# Apollon_ML_testing.net
KiCad netlist of a schematic drawn in EasyEDA
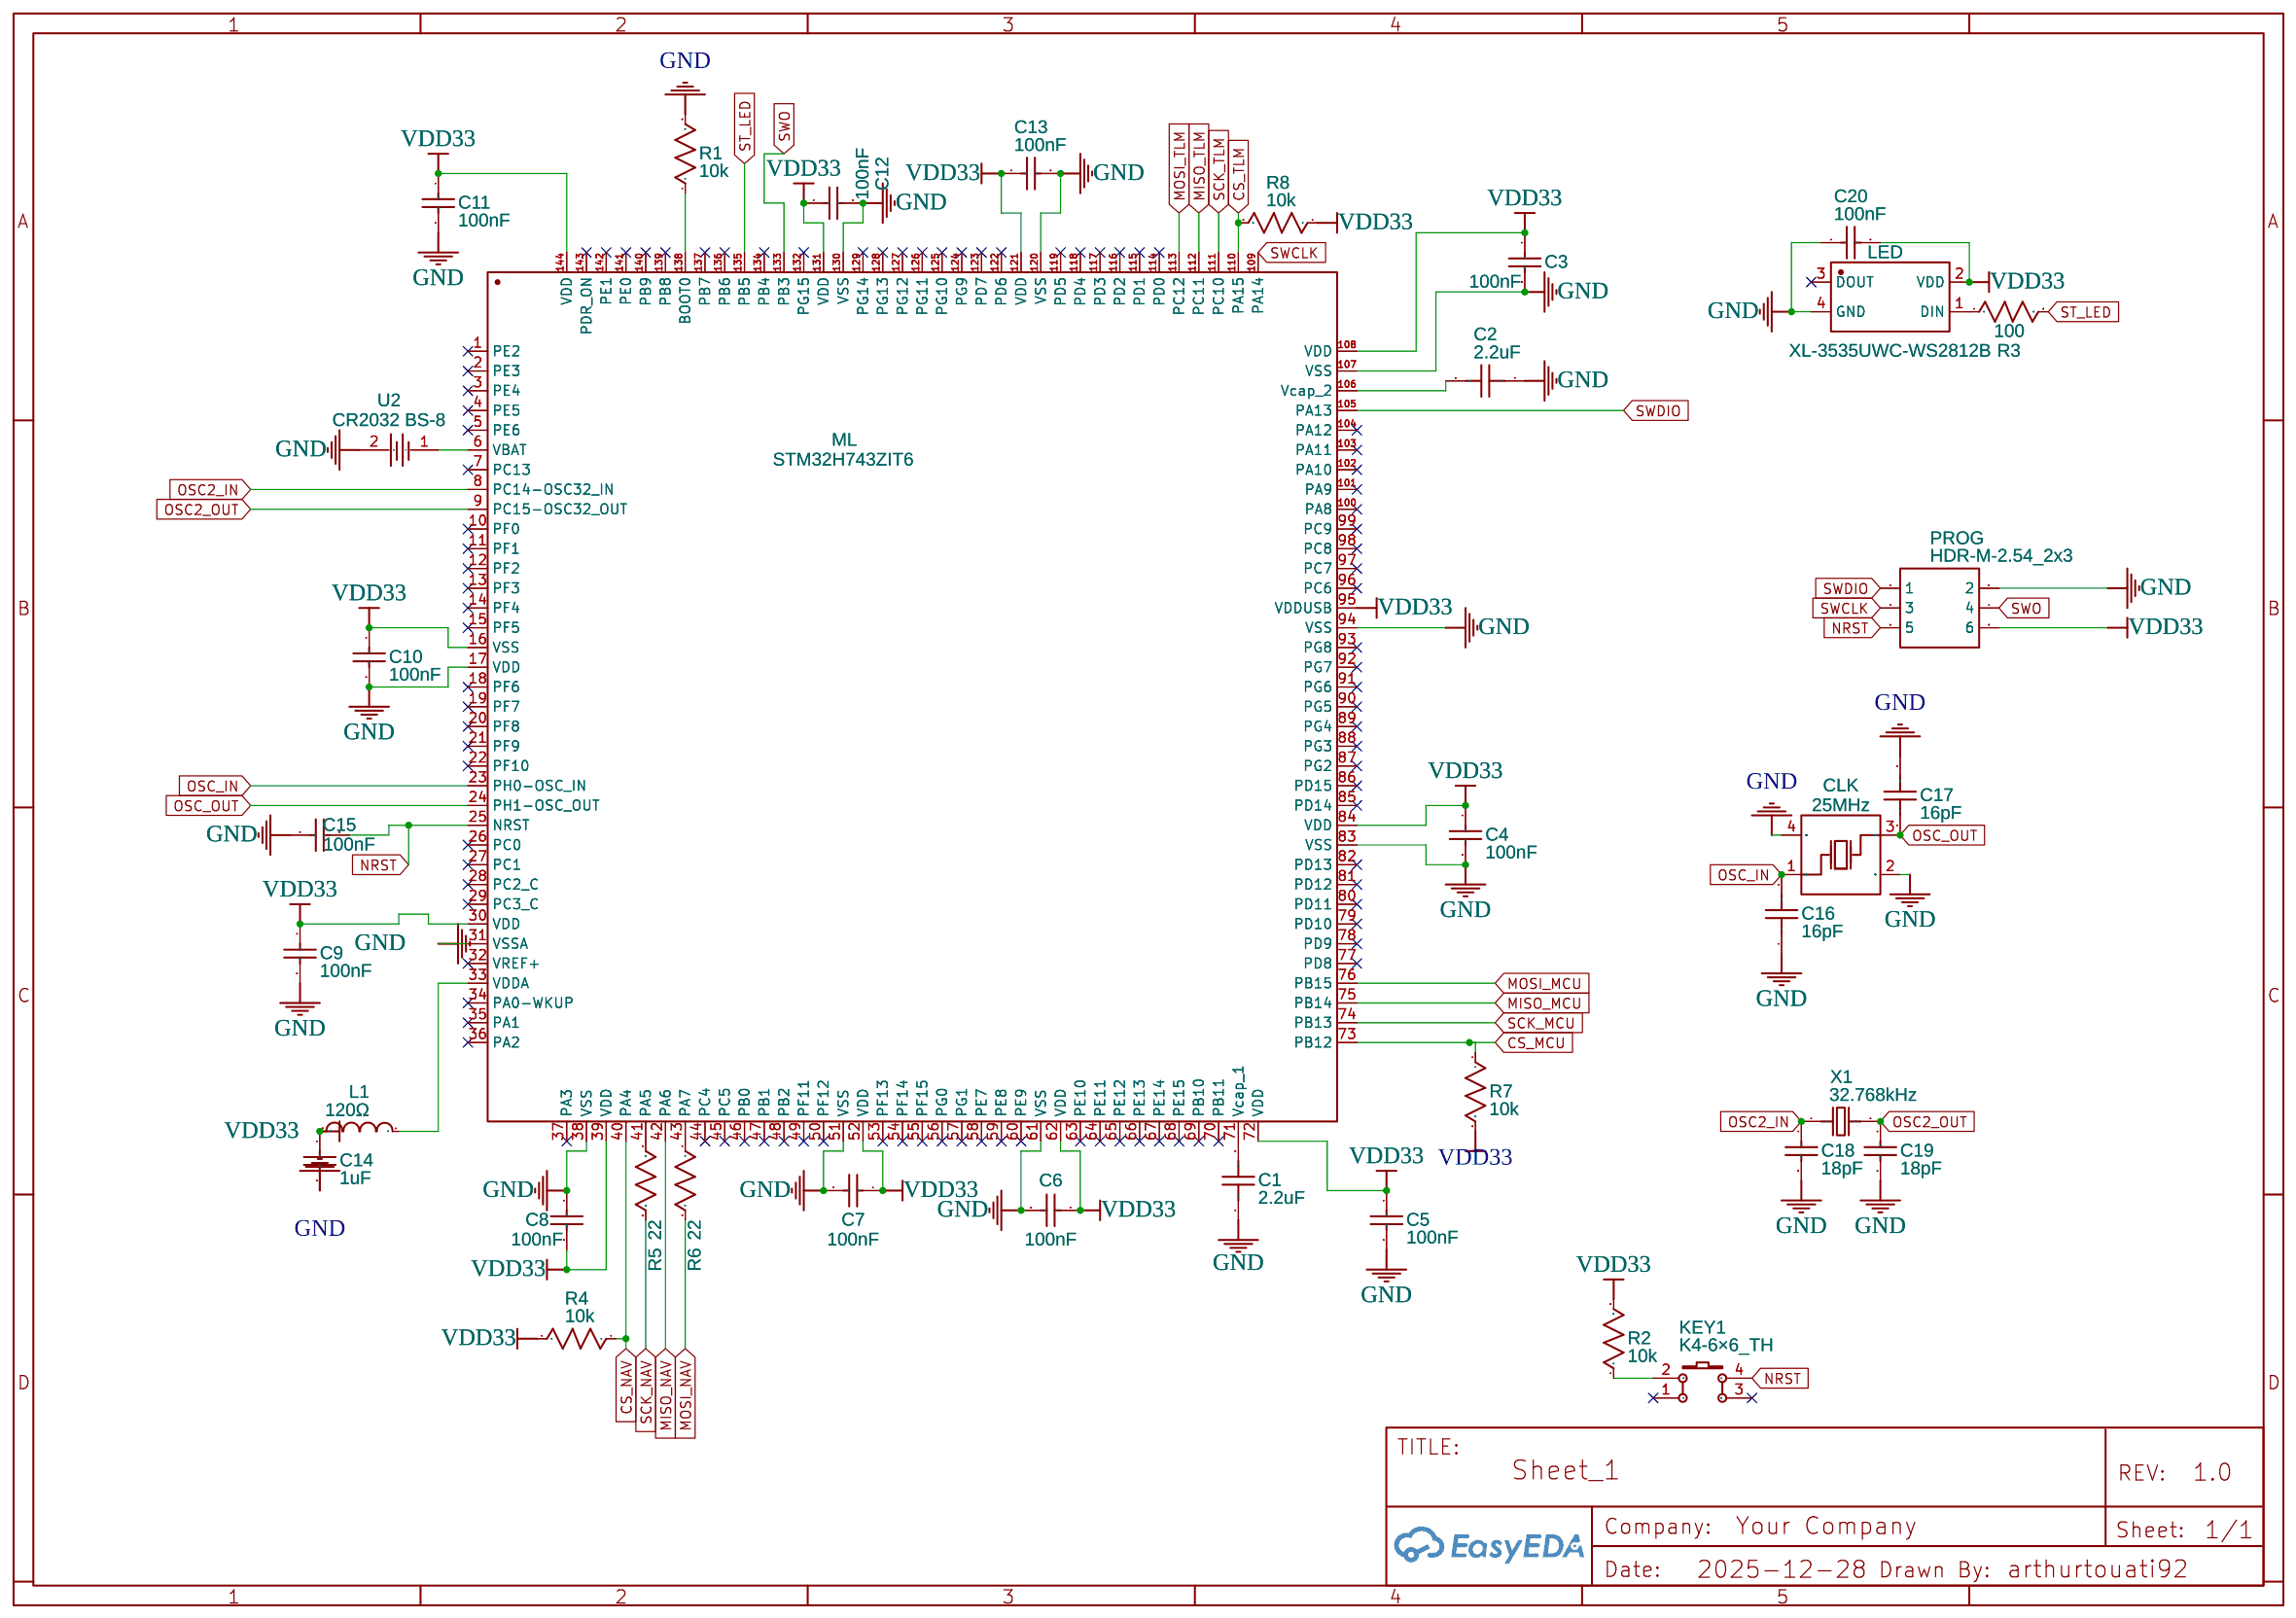
[diagram p0: schematic sheet]

(export (version "E")
  (design (tool "Eeschema 10.0.6"))
  (components
    (comp (ref "C1")
      (value "2.2uF")
      (fields
        (field (name "Manufacturer Part") "CL03A225MP3CRNC")
        (field (name "Manufacturer") "SAMSUNG(三星)")
      )
      (libsource (lib "") (part "CL03A225MP3CRNC_1"))
    )
    (comp (ref "C2")
      (value "2.2uF")
      (fields
        (field (name "Manufacturer Part") "CL03A225MP3CRNC")
        (field (name "Manufacturer") "SAMSUNG(三星)")
      )
      (libsource (lib "") (part "CL03A225MP3CRNC"))
    )
    (comp (ref "C3")
      (value "100nF")
      (fields
        (field (name "Manufacturer Part") "GRM033R61A104KE15D")
        (field (name "Manufacturer") "muRata(村田)")
      )
      (libsource (lib "") (part "GRM033R61A104KE15D"))
    )
    (comp (ref "C4")
      (value "100nF")
      (fields
        (field (name "Manufacturer Part") "GRM033R61A104KE15D")
        (field (name "Manufacturer") "muRata(村田)")
      )
      (libsource (lib "") (part "GRM033R61A104KE15D"))
    )
    (comp (ref "C5")
      (value "100nF")
      (fields
        (field (name "Manufacturer Part") "GRM033R61A104KE15D")
        (field (name "Manufacturer") "muRata(村田)")
      )
      (libsource (lib "") (part "GRM033R61A104KE15D"))
    )
    (comp (ref "C6")
      (value "100nF")
      (fields
        (field (name "Manufacturer Part") "GRM033R61A104KE15D")
        (field (name "Manufacturer") "muRata(村田)")
      )
      (libsource (lib "") (part "GRM033R61A104KE15D_2"))
    )
    (comp (ref "C7")
      (value "100nF")
      (fields
        (field (name "Manufacturer Part") "GRM033R61A104KE15D")
        (field (name "Manufacturer") "muRata(村田)")
      )
      (libsource (lib "") (part "GRM033R61A104KE15D_2"))
    )
    (comp (ref "C8")
      (value "100nF")
      (fields
        (field (name "Manufacturer Part") "GRM033R61A104KE15D")
        (field (name "Manufacturer") "muRata(村田)")
      )
      (libsource (lib "") (part "GRM033R61A104KE15D"))
    )
    (comp (ref "C9")
      (value "100nF")
      (fields
        (field (name "Manufacturer Part") "GRM033R61A104KE15D")
        (field (name "Manufacturer") "muRata(村田)")
      )
      (libsource (lib "") (part "GRM033R61A104KE15D"))
    )
    (comp (ref "C10")
      (value "100nF")
      (fields
        (field (name "Manufacturer Part") "GRM033R61A104KE15D")
        (field (name "Manufacturer") "muRata(村田)")
      )
      (libsource (lib "") (part "GRM033R61A104KE15D"))
    )
    (comp (ref "C11")
      (value "100nF")
      (fields
        (field (name "Manufacturer Part") "GRM033R61A104KE15D")
        (field (name "Manufacturer") "muRata(村田)")
      )
      (libsource (lib "") (part "GRM033R61A104KE15D"))
    )
    (comp (ref "C12")
      (value "100nF")
      (fields
        (field (name "Manufacturer Part") "GRM033R61A104KE15D")
        (field (name "Manufacturer") "muRata(村田)")
      )
      (libsource (lib "") (part "GRM033R61A104KE15D_1"))
    )
    (comp (ref "C13")
      (value "100nF")
      (fields
        (field (name "Manufacturer Part") "GRM033R61A104KE15D")
        (field (name "Manufacturer") "muRata(村田)")
      )
      (libsource (lib "") (part "GRM033R61A104KE15D_1"))
    )
    (comp (ref "C14")
      (value "1uF")
      (fields
        (field (name "Manufacturer Part") "CL03A105MQ3CSNH")
        (field (name "Manufacturer") "SAMSUNG(三星)")
      )
      (libsource (lib "") (part "CL03A105MQ3CSNH"))
    )
    (comp (ref "C15")
      (value "100nF")
      (fields
        (field (name "Manufacturer Part") "GRM033R61A104KE15D")
        (field (name "Manufacturer") "muRata(村田)")
      )
      (libsource (lib "") (part "GRM033R61A104KE15D_2"))
    )
    (comp (ref "C16")
      (value "16pF")
      (fields
        (field (name "Manufacturer Part") "GRM1555C1H160JA01D")
        (field (name "Manufacturer") "muRata(村田)")
      )
      (libsource (lib "") (part "GRM1555C1H160JA01D"))
    )
    (comp (ref "C17")
      (value "16pF")
      (fields
        (field (name "Manufacturer Part") "GRM1555C1H160JA01D")
        (field (name "Manufacturer") "muRata(村田)")
      )
      (libsource (lib "") (part "GRM1555C1H160JA01D"))
    )
    (comp (ref "C18")
      (value "18pF")
      (fields
        (field (name "Manufacturer Part") "GRM033R61A104KE15D")
        (field (name "Manufacturer") "muRata(村田)")
      )
      (libsource (lib "") (part "GRM033R61A104KE15D"))
    )
    (comp (ref "C19")
      (value "18pF")
      (fields
        (field (name "Manufacturer Part") "GRM033R61A104KE15D")
        (field (name "Manufacturer") "muRata(村田)")
      )
      (libsource (lib "") (part "GRM033R61A104KE15D"))
    )
    (comp (ref "C20")
      (value "100nF")
      (fields
        (field (name "Manufacturer Part") "GRM033R61A104KE15D")
        (field (name "Manufacturer") "muRata(村田)")
      )
      (libsource (lib "") (part "GRM033R61A104KE15D_1"))
    )
    (comp (ref "CLK")
      (value "25MHz")
      (fields
        (field (name "Manufacturer Part") "ABM8AIG-25.000MHZ-12-2Z-T3")
        (field (name "Manufacturer") "ABRACON")
      )
      (libsource (lib "") (part "ABM8AIG-25.000MHZ-12-2Z-T3"))
    )
    (comp (ref "KEY1")
      (value "K4-6×6_TH")
      (fields (field (name "Manufacturer Part") "K2-1102DP-E4SW-04") (field (name "Manufacturer") "韩国韩荣"))
      (libsource (lib "") (part "K4-6×6_TH"))
    )
    (comp (ref "L1")
      (value "120Ω")
      (fields (field (name "Manufacturer Part") "BLM03AG121SN1D") (field (name "Manufacturer") "muRata(村田)"))
      (libsource (lib "") (part "BLM03AG121SN1D"))
    )
    (comp (ref "LED")
      (value "XL-3535UWC-WS2812B")
      (fields
        (field (name "Manufacturer Part") "XL-3535UWC-2812B")
        (field (name "Manufacturer") "XINGLIGHT(成兴光)")
      )
      (libsource (lib "") (part "XL-3535UWC-WS2812B"))
    )
    (comp (ref "ML")
      (value "STM32H743ZIT6")
      (fields (field (name "Manufacturer") "ST(意法半导体)"))
      (libsource (lib "") (part "STM32H743ZIT6"))
    )
    (comp (ref "PROG") (value "HDR-M-2.54_2x3") (libsource (lib "") (part "HDR-M-2.54_2x3")))
    (comp (ref "R1") (value "10k") (libsource (lib "") (part "R_0201_US_2")))
    (comp (ref "R2") (value "10k") (libsource (lib "") (part "R_0201_US_2")))
    (comp (ref "R3") (value "100") (libsource (lib "") (part "R_0201_US_3")))
    (comp (ref "R4") (value "10k") (libsource (lib "") (part "R_0201_US_1")))
    (comp (ref "R5") (value "22") (libsource (lib "") (part "R_0201_US")))
    (comp (ref "R6") (value "22") (libsource (lib "") (part "R_0201_US")))
    (comp (ref "R7") (value "10k") (libsource (lib "") (part "R_0201_US")))
    (comp (ref "R8") (value "10k") (libsource (lib "") (part "R_0201_US_1")))
    (comp (ref "U2") (value "CR2032 BS-8") (libsource (lib "") (part "CR2032 BS-8")))
    (comp (ref "X1")
      (value "32.768kHz")
      (fields
        (field (name "Manufacturer Part") "SC-32S32.768kHz20PPM12.5pF")
        (field (name "Manufacturer") "Seiko(精工)")
      )
      (libsource (lib "") (part "SC-32S32.768kHz20PPM12.5pF"))
    )
  )
  (nets
    (net (code "1") (name "CS_MCU") (class "Default")
      (node (ref "ML") (pin "73") (pinfunction "PB12_73") (pintype "unspecified"))
      (node (ref "R7") (pin "1") (pinfunction "1_1") (pintype "unspecified"))
    )
    (net (code "2") (name "CS_NAV") (class "Default")
      (node (ref "ML") (pin "40") (pinfunction "PA4_40") (pintype "unspecified"))
      (node (ref "R4") (pin "1") (pinfunction "1_1") (pintype "unspecified"))
    )
    (net (code "3") (name "CS_TLM") (class "Default")
      (node (ref "ML") (pin "110") (pinfunction "PA15_110") (pintype "unspecified"))
      (node (ref "R8") (pin "2") (pinfunction "2_2") (pintype "unspecified"))
    )
    (net (code "4") (name "GND") (class "Default")
      (node (ref "C1") (pin "1") (pinfunction "1_1") (pintype "unspecified"))
      (node (ref "C10") (pin "2") (pinfunction "2_2") (pintype "input"))
      (node (ref "C11") (pin "2") (pinfunction "2_2") (pintype "input"))
      (node (ref "C12") (pin "2") (pinfunction "2_2") (pintype "input"))
      (node (ref "C13") (pin "2") (pinfunction "2_2") (pintype "input"))
      (node (ref "C14") (pin "2") (pinfunction "2_2") (pintype "input"))
      (node (ref "C15") (pin "2") (pinfunction "2_2") (pintype "input"))
      (node (ref "C16") (pin "1") (pinfunction "1_1") (pintype "unspecified"))
      (node (ref "C17") (pin "2") (pinfunction "2_2") (pintype "unspecified"))
      (node (ref "C18") (pin "2") (pinfunction "2_2") (pintype "input"))
      (node (ref "C19") (pin "2") (pinfunction "2_2") (pintype "input"))
      (node (ref "C2") (pin "1") (pinfunction "1_1") (pintype "unspecified"))
      (node (ref "C20") (pin "1") (pinfunction "1_1") (pintype "input"))
      (node (ref "C3") (pin "2") (pinfunction "2_2") (pintype "input"))
      (node (ref "C4") (pin "2") (pinfunction "2_2") (pintype "input"))
      (node (ref "C5") (pin "2") (pinfunction "2_2") (pintype "input"))
      (node (ref "C6") (pin "2") (pinfunction "2_2") (pintype "input"))
      (node (ref "C7") (pin "2") (pinfunction "2_2") (pintype "input"))
      (node (ref "C8") (pin "1") (pinfunction "1_1") (pintype "input"))
      (node (ref "C9") (pin "2") (pinfunction "2_2") (pintype "input"))
      (node (ref "CLK") (pin "2") (pinfunction "GND_2") (pintype "unspecified"))
      (node (ref "CLK") (pin "4") (pinfunction "GND_4") (pintype "unspecified"))
      (node (ref "LED") (pin "4") (pinfunction "GND_4") (pintype "unspecified"))
      (node (ref "ML") (pin "107") (pinfunction "VSS_107") (pintype "unspecified"))
      (node (ref "ML") (pin "120") (pinfunction "VSS_120") (pintype "unspecified"))
      (node (ref "ML") (pin "130") (pinfunction "VSS_130") (pintype "unspecified"))
      (node (ref "ML") (pin "17") (pinfunction "VDD_17") (pintype "unspecified"))
      (node (ref "ML") (pin "31") (pinfunction "VSSA_31") (pintype "unspecified"))
      (node (ref "ML") (pin "38") (pinfunction "VSS_38") (pintype "unspecified"))
      (node (ref "ML") (pin "51") (pinfunction "VSS_51") (pintype "unspecified"))
      (node (ref "ML") (pin "61") (pinfunction "VSS_61") (pintype "unspecified"))
      (node (ref "ML") (pin "83") (pinfunction "VSS_83") (pintype "unspecified"))
      (node (ref "ML") (pin "94") (pinfunction "VSS_94") (pintype "unspecified"))
      (node (ref "PROG") (pin "2") (pinfunction "2_2") (pintype "input"))
      (node (ref "R1") (pin "2") (pinfunction "2_2") (pintype "unspecified"))
      (node (ref "U2") (pin "2") (pinfunction "+_2") (pintype "input"))
    )
    (net (code "5") (name "MISO_MCU") (class "Default")
      (node (ref "ML") (pin "75") (pinfunction "PB14_75") (pintype "unspecified"))
    )
    (net (code "6") (name "MISO_NAV") (class "Default")
      (node (ref "ML") (pin "42") (pinfunction "PA6_42") (pintype "unspecified"))
    )
    (net (code "7") (name "MISO_TLM") (class "Default")
      (node (ref "ML") (pin "112") (pinfunction "PC11_112") (pintype "unspecified"))
    )
    (net (code "8") (name "MOSI_MCU") (class "Default")
      (node (ref "ML") (pin "76") (pinfunction "PB15_76") (pintype "unspecified"))
    )
    (net (code "9") (name "MOSI_NAV") (class "Default")
      (node (ref "R6") (pin "2") (pinfunction "2_2") (pintype "unspecified"))
    )
    (net (code "10") (name "MOSI_TLM") (class "Default")
      (node (ref "ML") (pin "113") (pinfunction "PC12_113") (pintype "unspecified"))
    )
    (net (code "11") (name "NRST") (class "Default")
      (node (ref "C15") (pin "1") (pinfunction "1_1") (pintype "input"))
      (node (ref "KEY1") (pin "4") (pinfunction "4_4") (pintype "unspecified"))
      (node (ref "ML") (pin "25") (pinfunction "NRST_25") (pintype "unspecified"))
      (node (ref "PROG") (pin "5") (pinfunction "5_5") (pintype "input"))
    )
    (net (code "12") (name "Net-(KEY1-Pad2)") (class "Default")
      (node (ref "KEY1") (pin "2") (pinfunction "2_2") (pintype "unspecified"))
      (node (ref "R2") (pin "1") (pinfunction "1_1") (pintype "unspecified"))
    )
    (net (code "13") (name "Net-(LED-DIN)") (class "Default")
      (node (ref "LED") (pin "1") (pinfunction "DIN_1") (pintype "unspecified"))
      (node (ref "R3") (pin "1") (pinfunction "1_1") (pintype "unspecified"))
    )
    (net (code "14") (name "Net-(ML-BOOT0)") (class "Default")
      (node (ref "ML") (pin "138") (pinfunction "BOOT0_138") (pintype "unspecified"))
      (node (ref "R1") (pin "1") (pinfunction "1_1") (pintype "unspecified"))
    )
    (net (code "15") (name "Net-(ML-PA5)") (class "Default")
      (node (ref "ML") (pin "41") (pinfunction "PA5_41") (pintype "unspecified"))
      (node (ref "R5") (pin "1") (pinfunction "1_1") (pintype "unspecified"))
    )
    (net (code "16") (name "Net-(ML-PA7)") (class "Default")
      (node (ref "ML") (pin "43") (pinfunction "PA7_43") (pintype "unspecified"))
      (node (ref "R6") (pin "1") (pinfunction "1_1") (pintype "unspecified"))
    )
    (net (code "17") (name "Net-(ML-VBAT)") (class "Default")
      (node (ref "ML") (pin "6") (pinfunction "VBAT_6") (pintype "unspecified"))
      (node (ref "U2") (pin "1") (pinfunction "-_1") (pintype "input"))
    )
    (net (code "18") (name "Net-(ML-VDDA)") (class "Default")
      (node (ref "L1") (pin "1") (pinfunction "1_1") (pintype "unspecified"))
      (node (ref "ML") (pin "33") (pinfunction "VDDA_33") (pintype "unspecified"))
    )
    (net (code "19") (name "Net-(ML-Vcap_1)") (class "Default")
      (node (ref "C1") (pin "2") (pinfunction "2_2") (pintype "unspecified"))
      (node (ref "ML") (pin "71") (pinfunction "Vcap_1_71") (pintype "unspecified"))
    )
    (net (code "20") (name "Net-(ML-Vcap_2)") (class "Default")
      (node (ref "C2") (pin "2") (pinfunction "2_2") (pintype "unspecified"))
      (node (ref "ML") (pin "106") (pinfunction "Vcap_2_106") (pintype "unspecified"))
    )
    (net (code "21") (name "OSC2_IN") (class "Default")
      (node (ref "C18") (pin "1") (pinfunction "1_1") (pintype "input"))
      (node (ref "ML") (pin "8") (pinfunction "PC14-OSC32_IN_8") (pintype "unspecified"))
      (node (ref "X1") (pin "1") (pinfunction "1_1") (pintype "unspecified"))
    )
    (net (code "22") (name "OSC2_OUT") (class "Default")
      (node (ref "C19") (pin "1") (pinfunction "1_1") (pintype "input"))
      (node (ref "ML") (pin "9") (pinfunction "PC15-OSC32_OUT_9") (pintype "unspecified"))
      (node (ref "X1") (pin "2") (pinfunction "2_2") (pintype "unspecified"))
    )
    (net (code "23") (name "OSC_IN") (class "Default")
      (node (ref "C16") (pin "2") (pinfunction "2_2") (pintype "unspecified"))
      (node (ref "CLK") (pin "1") (pinfunction "OSC1_1") (pintype "unspecified"))
      (node (ref "ML") (pin "23") (pinfunction "PH0-OSC_IN_23") (pintype "unspecified"))
    )
    (net (code "24") (name "OSC_OUT") (class "Default")
      (node (ref "C17") (pin "1") (pinfunction "1_1") (pintype "unspecified"))
      (node (ref "CLK") (pin "3") (pinfunction "OSC2_3") (pintype "unspecified"))
      (node (ref "ML") (pin "24") (pinfunction "PH1-OSC_OUT_24") (pintype "unspecified"))
    )
    (net (code "25") (name "SCK_MCU") (class "Default")
      (node (ref "ML") (pin "74") (pinfunction "PB13_74") (pintype "unspecified"))
    )
    (net (code "26") (name "SCK_NAV") (class "Default")
      (node (ref "R5") (pin "2") (pinfunction "2_2") (pintype "unspecified"))
    )
    (net (code "27") (name "SCK_TLM") (class "Default")
      (node (ref "ML") (pin "111") (pinfunction "PC10_111") (pintype "unspecified"))
    )
    (net (code "28") (name "ST_LED") (class "Default")
      (node (ref "ML") (pin "135") (pinfunction "PB5_135") (pintype "unspecified"))
      (node (ref "R3") (pin "2") (pinfunction "2_2") (pintype "unspecified"))
    )
    (net (code "29") (name "SWCLK") (class "Default")
      (node (ref "ML") (pin "109") (pinfunction "PA14_109") (pintype "unspecified"))
      (node (ref "PROG") (pin "3") (pinfunction "3_3") (pintype "input"))
    )
    (net (code "30") (name "SWDIO") (class "Default")
      (node (ref "ML") (pin "105") (pinfunction "PA13_105") (pintype "unspecified"))
      (node (ref "PROG") (pin "1") (pinfunction "1_1") (pintype "input"))
    )
    (net (code "31") (name "SWO") (class "Default")
      (node (ref "ML") (pin "133") (pinfunction "PB3_133") (pintype "unspecified"))
      (node (ref "PROG") (pin "4") (pinfunction "4_4") (pintype "input"))
    )
    (net (code "32") (name "VDD33") (class "Default")
      (node (ref "C10") (pin "1") (pinfunction "1_1") (pintype "input"))
      (node (ref "C11") (pin "1") (pinfunction "1_1") (pintype "input"))
      (node (ref "C12") (pin "1") (pinfunction "1_1") (pintype "input"))
      (node (ref "C13") (pin "1") (pinfunction "1_1") (pintype "input"))
      (node (ref "C14") (pin "1") (pinfunction "1_1") (pintype "input"))
      (node (ref "C20") (pin "2") (pinfunction "2_2") (pintype "input"))
      (node (ref "C3") (pin "1") (pinfunction "1_1") (pintype "input"))
      (node (ref "C4") (pin "1") (pinfunction "1_1") (pintype "input"))
      (node (ref "C5") (pin "1") (pinfunction "1_1") (pintype "input"))
      (node (ref "C6") (pin "1") (pinfunction "1_1") (pintype "input"))
      (node (ref "C7") (pin "1") (pinfunction "1_1") (pintype "input"))
      (node (ref "C8") (pin "2") (pinfunction "2_2") (pintype "input"))
      (node (ref "C9") (pin "1") (pinfunction "1_1") (pintype "input"))
      (node (ref "L1") (pin "2") (pinfunction "2_2") (pintype "unspecified"))
      (node (ref "LED") (pin "2") (pinfunction "VDD_2") (pintype "unspecified"))
      (node (ref "ML") (pin "108") (pinfunction "VDD_108") (pintype "unspecified"))
      (node (ref "ML") (pin "121") (pinfunction "VDD_121") (pintype "unspecified"))
      (node (ref "ML") (pin "131") (pinfunction "VDD_131") (pintype "unspecified"))
      (node (ref "ML") (pin "144") (pinfunction "VDD_144") (pintype "unspecified"))
      (node (ref "ML") (pin "16") (pinfunction "VSS_16") (pintype "unspecified"))
      (node (ref "ML") (pin "30") (pinfunction "VDD_30") (pintype "unspecified"))
      (node (ref "ML") (pin "39") (pinfunction "VDD_39") (pintype "unspecified"))
      (node (ref "ML") (pin "52") (pinfunction "VDD_52") (pintype "unspecified"))
      (node (ref "ML") (pin "62") (pinfunction "VDD_62") (pintype "unspecified"))
      (node (ref "ML") (pin "72") (pinfunction "VDD_72") (pintype "unspecified"))
      (node (ref "ML") (pin "84") (pinfunction "VDD_84") (pintype "unspecified"))
      (node (ref "ML") (pin "95") (pinfunction "VDDUSB_95") (pintype "unspecified"))
      (node (ref "PROG") (pin "6") (pinfunction "6_6") (pintype "input"))
      (node (ref "R2") (pin "2") (pinfunction "2_2") (pintype "unspecified"))
      (node (ref "R4") (pin "2") (pinfunction "2_2") (pintype "unspecified"))
      (node (ref "R7") (pin "2") (pinfunction "2_2") (pintype "unspecified"))
      (node (ref "R8") (pin "1") (pinfunction "1_1") (pintype "unspecified"))
    )
    (net (code "33") (name "unconnected-(KEY1-Pad1)") (class "Default")
      (node (ref "KEY1") (pin "1") (pinfunction "1_1") (pintype "unspecified+no_connect"))
    )
    (net (code "34") (name "unconnected-(KEY1-Pad3)") (class "Default")
      (node (ref "KEY1") (pin "3") (pinfunction "3_3") (pintype "unspecified+no_connect"))
    )
    (net (code "35") (name "unconnected-(LED-DOUT-Pad3)") (class "Default")
      (node (ref "LED") (pin "3") (pinfunction "DOUT_3") (pintype "unspecified+no_connect"))
    )
    (net (code "36") (name "unconnected-(ML-PA0-WKUP-Pad34)") (class "Default")
      (node (ref "ML") (pin "34") (pinfunction "PA0-WKUP_34") (pintype "unspecified+no_connect"))
    )
    (net (code "37") (name "unconnected-(ML-PA1-Pad35)") (class "Default")
      (node (ref "ML") (pin "35") (pinfunction "PA1_35") (pintype "unspecified+no_connect"))
    )
    (net (code "38") (name "unconnected-(ML-PA2-Pad36)") (class "Default")
      (node (ref "ML") (pin "36") (pinfunction "PA2_36") (pintype "unspecified+no_connect"))
    )
    (net (code "39") (name "unconnected-(ML-PA3-Pad37)") (class "Default")
      (node (ref "ML") (pin "37") (pinfunction "PA3_37") (pintype "unspecified+no_connect"))
    )
    (net (code "40") (name "unconnected-(ML-PA8-Pad100)") (class "Default")
      (node (ref "ML") (pin "100") (pinfunction "PA8_100") (pintype "unspecified+no_connect"))
    )
    (net (code "41") (name "unconnected-(ML-PA9-Pad101)") (class "Default")
      (node (ref "ML") (pin "101") (pinfunction "PA9_101") (pintype "unspecified+no_connect"))
    )
    (net (code "42") (name "unconnected-(ML-PA10-Pad102)") (class "Default")
      (node (ref "ML") (pin "102") (pinfunction "PA10_102") (pintype "unspecified+no_connect"))
    )
    (net (code "43") (name "unconnected-(ML-PA11-Pad103)") (class "Default")
      (node (ref "ML") (pin "103") (pinfunction "PA11_103") (pintype "unspecified+no_connect"))
    )
    (net (code "44") (name "unconnected-(ML-PA12-Pad104)") (class "Default")
      (node (ref "ML") (pin "104") (pinfunction "PA12_104") (pintype "unspecified+no_connect"))
    )
    (net (code "45") (name "unconnected-(ML-PB0-Pad46)") (class "Default")
      (node (ref "ML") (pin "46") (pinfunction "PB0_46") (pintype "unspecified+no_connect"))
    )
    (net (code "46") (name "unconnected-(ML-PB1-Pad47)") (class "Default")
      (node (ref "ML") (pin "47") (pinfunction "PB1_47") (pintype "unspecified+no_connect"))
    )
    (net (code "47") (name "unconnected-(ML-PB2-Pad48)") (class "Default")
      (node (ref "ML") (pin "48") (pinfunction "PB2_48") (pintype "unspecified+no_connect"))
    )
    (net (code "48") (name "unconnected-(ML-PB4-Pad134)") (class "Default")
      (node (ref "ML") (pin "134") (pinfunction "PB4_134") (pintype "unspecified+no_connect"))
    )
    (net (code "49") (name "unconnected-(ML-PB6-Pad136)") (class "Default")
      (node (ref "ML") (pin "136") (pinfunction "PB6_136") (pintype "unspecified+no_connect"))
    )
    (net (code "50") (name "unconnected-(ML-PB7-Pad137)") (class "Default")
      (node (ref "ML") (pin "137") (pinfunction "PB7_137") (pintype "unspecified+no_connect"))
    )
    (net (code "51") (name "unconnected-(ML-PB8-Pad139)") (class "Default")
      (node (ref "ML") (pin "139") (pinfunction "PB8_139") (pintype "unspecified+no_connect"))
    )
    (net (code "52") (name "unconnected-(ML-PB9-Pad140)") (class "Default")
      (node (ref "ML") (pin "140") (pinfunction "PB9_140") (pintype "unspecified+no_connect"))
    )
    (net (code "53") (name "unconnected-(ML-PB10-Pad69)") (class "Default")
      (node (ref "ML") (pin "69") (pinfunction "PB10_69") (pintype "unspecified+no_connect"))
    )
    (net (code "54") (name "unconnected-(ML-PB11-Pad70)") (class "Default")
      (node (ref "ML") (pin "70") (pinfunction "PB11_70") (pintype "unspecified+no_connect"))
    )
    (net (code "55") (name "unconnected-(ML-PC0-Pad26)") (class "Default")
      (node (ref "ML") (pin "26") (pinfunction "PC0_26") (pintype "unspecified+no_connect"))
    )
    (net (code "56") (name "unconnected-(ML-PC1-Pad27)") (class "Default")
      (node (ref "ML") (pin "27") (pinfunction "PC1_27") (pintype "unspecified+no_connect"))
    )
    (net (code "57") (name "unconnected-(ML-PC2_C-Pad28)") (class "Default")
      (node (ref "ML") (pin "28") (pinfunction "PC2_C_28") (pintype "unspecified+no_connect"))
    )
    (net (code "58") (name "unconnected-(ML-PC3_C-Pad29)") (class "Default")
      (node (ref "ML") (pin "29") (pinfunction "PC3_C_29") (pintype "unspecified+no_connect"))
    )
    (net (code "59") (name "unconnected-(ML-PC4-Pad44)") (class "Default")
      (node (ref "ML") (pin "44") (pinfunction "PC4_44") (pintype "unspecified+no_connect"))
    )
    (net (code "60") (name "unconnected-(ML-PC5-Pad45)") (class "Default")
      (node (ref "ML") (pin "45") (pinfunction "PC5_45") (pintype "unspecified+no_connect"))
    )
    (net (code "61") (name "unconnected-(ML-PC6-Pad96)") (class "Default")
      (node (ref "ML") (pin "96") (pinfunction "PC6_96") (pintype "unspecified+no_connect"))
    )
    (net (code "62") (name "unconnected-(ML-PC7-Pad97)") (class "Default")
      (node (ref "ML") (pin "97") (pinfunction "PC7_97") (pintype "unspecified+no_connect"))
    )
    (net (code "63") (name "unconnected-(ML-PC8-Pad98)") (class "Default")
      (node (ref "ML") (pin "98") (pinfunction "PC8_98") (pintype "unspecified+no_connect"))
    )
    (net (code "64") (name "unconnected-(ML-PC9-Pad99)") (class "Default")
      (node (ref "ML") (pin "99") (pinfunction "PC9_99") (pintype "unspecified+no_connect"))
    )
    (net (code "65") (name "unconnected-(ML-PC13-Pad7)") (class "Default")
      (node (ref "ML") (pin "7") (pinfunction "PC13_7") (pintype "unspecified+no_connect"))
    )
    (net (code "66") (name "unconnected-(ML-PD0-Pad114)") (class "Default")
      (node (ref "ML") (pin "114") (pinfunction "PD0_114") (pintype "unspecified+no_connect"))
    )
    (net (code "67") (name "unconnected-(ML-PD1-Pad115)") (class "Default")
      (node (ref "ML") (pin "115") (pinfunction "PD1_115") (pintype "unspecified+no_connect"))
    )
    (net (code "68") (name "unconnected-(ML-PD2-Pad116)") (class "Default")
      (node (ref "ML") (pin "116") (pinfunction "PD2_116") (pintype "unspecified+no_connect"))
    )
    (net (code "69") (name "unconnected-(ML-PD3-Pad117)") (class "Default")
      (node (ref "ML") (pin "117") (pinfunction "PD3_117") (pintype "unspecified+no_connect"))
    )
    (net (code "70") (name "unconnected-(ML-PD4-Pad118)") (class "Default")
      (node (ref "ML") (pin "118") (pinfunction "PD4_118") (pintype "unspecified+no_connect"))
    )
    (net (code "71") (name "unconnected-(ML-PD5-Pad119)") (class "Default")
      (node (ref "ML") (pin "119") (pinfunction "PD5_119") (pintype "unspecified+no_connect"))
    )
    (net (code "72") (name "unconnected-(ML-PD6-Pad122)") (class "Default")
      (node (ref "ML") (pin "122") (pinfunction "PD6_122") (pintype "unspecified+no_connect"))
    )
    (net (code "73") (name "unconnected-(ML-PD7-Pad123)") (class "Default")
      (node (ref "ML") (pin "123") (pinfunction "PD7_123") (pintype "unspecified+no_connect"))
    )
    (net (code "74") (name "unconnected-(ML-PD8-Pad77)") (class "Default")
      (node (ref "ML") (pin "77") (pinfunction "PD8_77") (pintype "unspecified+no_connect"))
    )
    (net (code "75") (name "unconnected-(ML-PD9-Pad78)") (class "Default")
      (node (ref "ML") (pin "78") (pinfunction "PD9_78") (pintype "unspecified+no_connect"))
    )
    (net (code "76") (name "unconnected-(ML-PD10-Pad79)") (class "Default")
      (node (ref "ML") (pin "79") (pinfunction "PD10_79") (pintype "unspecified+no_connect"))
    )
    (net (code "77") (name "unconnected-(ML-PD11-Pad80)") (class "Default")
      (node (ref "ML") (pin "80") (pinfunction "PD11_80") (pintype "unspecified+no_connect"))
    )
    (net (code "78") (name "unconnected-(ML-PD12-Pad81)") (class "Default")
      (node (ref "ML") (pin "81") (pinfunction "PD12_81") (pintype "unspecified+no_connect"))
    )
    (net (code "79") (name "unconnected-(ML-PD13-Pad82)") (class "Default")
      (node (ref "ML") (pin "82") (pinfunction "PD13_82") (pintype "unspecified+no_connect"))
    )
    (net (code "80") (name "unconnected-(ML-PD14-Pad85)") (class "Default")
      (node (ref "ML") (pin "85") (pinfunction "PD14_85") (pintype "unspecified+no_connect"))
    )
    (net (code "81") (name "unconnected-(ML-PD15-Pad86)") (class "Default")
      (node (ref "ML") (pin "86") (pinfunction "PD15_86") (pintype "unspecified+no_connect"))
    )
    (net (code "82") (name "unconnected-(ML-PDR_ON-Pad143)") (class "Default")
      (node (ref "ML") (pin "143") (pinfunction "PDR_ON_143") (pintype "unspecified+no_connect"))
    )
    (net (code "83") (name "unconnected-(ML-PE0-Pad141)") (class "Default")
      (node (ref "ML") (pin "141") (pinfunction "PE0_141") (pintype "unspecified+no_connect"))
    )
    (net (code "84") (name "unconnected-(ML-PE1-Pad142)") (class "Default")
      (node (ref "ML") (pin "142") (pinfunction "PE1_142") (pintype "unspecified+no_connect"))
    )
    (net (code "85") (name "unconnected-(ML-PE2-Pad1)") (class "Default")
      (node (ref "ML") (pin "1") (pinfunction "PE2_1") (pintype "unspecified+no_connect"))
    )
    (net (code "86") (name "unconnected-(ML-PE3-Pad2)") (class "Default")
      (node (ref "ML") (pin "2") (pinfunction "PE3_2") (pintype "unspecified+no_connect"))
    )
    (net (code "87") (name "unconnected-(ML-PE4-Pad3)") (class "Default")
      (node (ref "ML") (pin "3") (pinfunction "PE4_3") (pintype "unspecified+no_connect"))
    )
    (net (code "88") (name "unconnected-(ML-PE5-Pad4)") (class "Default")
      (node (ref "ML") (pin "4") (pinfunction "PE5_4") (pintype "unspecified+no_connect"))
    )
    (net (code "89") (name "unconnected-(ML-PE6-Pad5)") (class "Default")
      (node (ref "ML") (pin "5") (pinfunction "PE6_5") (pintype "unspecified+no_connect"))
    )
    (net (code "90") (name "unconnected-(ML-PE7-Pad58)") (class "Default")
      (node (ref "ML") (pin "58") (pinfunction "PE7_58") (pintype "unspecified+no_connect"))
    )
    (net (code "91") (name "unconnected-(ML-PE8-Pad59)") (class "Default")
      (node (ref "ML") (pin "59") (pinfunction "PE8_59") (pintype "unspecified+no_connect"))
    )
    (net (code "92") (name "unconnected-(ML-PE9-Pad60)") (class "Default")
      (node (ref "ML") (pin "60") (pinfunction "PE9_60") (pintype "unspecified+no_connect"))
    )
    (net (code "93") (name "unconnected-(ML-PE10-Pad63)") (class "Default")
      (node (ref "ML") (pin "63") (pinfunction "PE10_63") (pintype "unspecified+no_connect"))
    )
    (net (code "94") (name "unconnected-(ML-PE11-Pad64)") (class "Default")
      (node (ref "ML") (pin "64") (pinfunction "PE11_64") (pintype "unspecified+no_connect"))
    )
    (net (code "95") (name "unconnected-(ML-PE12-Pad65)") (class "Default")
      (node (ref "ML") (pin "65") (pinfunction "PE12_65") (pintype "unspecified+no_connect"))
    )
    (net (code "96") (name "unconnected-(ML-PE13-Pad66)") (class "Default")
      (node (ref "ML") (pin "66") (pinfunction "PE13_66") (pintype "unspecified+no_connect"))
    )
    (net (code "97") (name "unconnected-(ML-PE14-Pad67)") (class "Default")
      (node (ref "ML") (pin "67") (pinfunction "PE14_67") (pintype "unspecified+no_connect"))
    )
    (net (code "98") (name "unconnected-(ML-PE15-Pad68)") (class "Default")
      (node (ref "ML") (pin "68") (pinfunction "PE15_68") (pintype "unspecified+no_connect"))
    )
    (net (code "99") (name "unconnected-(ML-PF0-Pad10)") (class "Default")
      (node (ref "ML") (pin "10") (pinfunction "PF0_10") (pintype "unspecified+no_connect"))
    )
    (net (code "100") (name "unconnected-(ML-PF1-Pad11)") (class "Default")
      (node (ref "ML") (pin "11") (pinfunction "PF1_11") (pintype "unspecified+no_connect"))
    )
    (net (code "101") (name "unconnected-(ML-PF2-Pad12)") (class "Default")
      (node (ref "ML") (pin "12") (pinfunction "PF2_12") (pintype "unspecified+no_connect"))
    )
    (net (code "102") (name "unconnected-(ML-PF3-Pad13)") (class "Default")
      (node (ref "ML") (pin "13") (pinfunction "PF3_13") (pintype "unspecified+no_connect"))
    )
    (net (code "103") (name "unconnected-(ML-PF4-Pad14)") (class "Default")
      (node (ref "ML") (pin "14") (pinfunction "PF4_14") (pintype "unspecified+no_connect"))
    )
    (net (code "104") (name "unconnected-(ML-PF5-Pad15)") (class "Default")
      (node (ref "ML") (pin "15") (pinfunction "PF5_15") (pintype "unspecified+no_connect"))
    )
    (net (code "105") (name "unconnected-(ML-PF6-Pad18)") (class "Default")
      (node (ref "ML") (pin "18") (pinfunction "PF6_18") (pintype "unspecified+no_connect"))
    )
    (net (code "106") (name "unconnected-(ML-PF7-Pad19)") (class "Default")
      (node (ref "ML") (pin "19") (pinfunction "PF7_19") (pintype "unspecified+no_connect"))
    )
    (net (code "107") (name "unconnected-(ML-PF8-Pad20)") (class "Default")
      (node (ref "ML") (pin "20") (pinfunction "PF8_20") (pintype "unspecified+no_connect"))
    )
    (net (code "108") (name "unconnected-(ML-PF9-Pad21)") (class "Default")
      (node (ref "ML") (pin "21") (pinfunction "PF9_21") (pintype "unspecified+no_connect"))
    )
    (net (code "109") (name "unconnected-(ML-PF10-Pad22)") (class "Default")
      (node (ref "ML") (pin "22") (pinfunction "PF10_22") (pintype "unspecified+no_connect"))
    )
    (net (code "110") (name "unconnected-(ML-PF11-Pad49)") (class "Default")
      (node (ref "ML") (pin "49") (pinfunction "PF11_49") (pintype "unspecified+no_connect"))
    )
    (net (code "111") (name "unconnected-(ML-PF12-Pad50)") (class "Default")
      (node (ref "ML") (pin "50") (pinfunction "PF12_50") (pintype "unspecified+no_connect"))
    )
    (net (code "112") (name "unconnected-(ML-PF13-Pad53)") (class "Default")
      (node (ref "ML") (pin "53") (pinfunction "PF13_53") (pintype "unspecified+no_connect"))
    )
    (net (code "113") (name "unconnected-(ML-PF14-Pad54)") (class "Default")
      (node (ref "ML") (pin "54") (pinfunction "PF14_54") (pintype "unspecified+no_connect"))
    )
    (net (code "114") (name "unconnected-(ML-PF15-Pad55)") (class "Default")
      (node (ref "ML") (pin "55") (pinfunction "PF15_55") (pintype "unspecified+no_connect"))
    )
    (net (code "115") (name "unconnected-(ML-PG0-Pad56)") (class "Default")
      (node (ref "ML") (pin "56") (pinfunction "PG0_56") (pintype "unspecified+no_connect"))
    )
    (net (code "116") (name "unconnected-(ML-PG1-Pad57)") (class "Default")
      (node (ref "ML") (pin "57") (pinfunction "PG1_57") (pintype "unspecified+no_connect"))
    )
    (net (code "117") (name "unconnected-(ML-PG2-Pad87)") (class "Default")
      (node (ref "ML") (pin "87") (pinfunction "PG2_87") (pintype "unspecified+no_connect"))
    )
    (net (code "118") (name "unconnected-(ML-PG3-Pad88)") (class "Default")
      (node (ref "ML") (pin "88") (pinfunction "PG3_88") (pintype "unspecified+no_connect"))
    )
    (net (code "119") (name "unconnected-(ML-PG4-Pad89)") (class "Default")
      (node (ref "ML") (pin "89") (pinfunction "PG4_89") (pintype "unspecified+no_connect"))
    )
    (net (code "120") (name "unconnected-(ML-PG5-Pad90)") (class "Default")
      (node (ref "ML") (pin "90") (pinfunction "PG5_90") (pintype "unspecified+no_connect"))
    )
    (net (code "121") (name "unconnected-(ML-PG6-Pad91)") (class "Default")
      (node (ref "ML") (pin "91") (pinfunction "PG6_91") (pintype "unspecified+no_connect"))
    )
    (net (code "122") (name "unconnected-(ML-PG7-Pad92)") (class "Default")
      (node (ref "ML") (pin "92") (pinfunction "PG7_92") (pintype "unspecified+no_connect"))
    )
    (net (code "123") (name "unconnected-(ML-PG8-Pad93)") (class "Default")
      (node (ref "ML") (pin "93") (pinfunction "PG8_93") (pintype "unspecified+no_connect"))
    )
    (net (code "124") (name "unconnected-(ML-PG9-Pad124)") (class "Default")
      (node (ref "ML") (pin "124") (pinfunction "PG9_124") (pintype "unspecified+no_connect"))
    )
    (net (code "125") (name "unconnected-(ML-PG10-Pad125)") (class "Default")
      (node (ref "ML") (pin "125") (pinfunction "PG10_125") (pintype "unspecified+no_connect"))
    )
    (net (code "126") (name "unconnected-(ML-PG11-Pad126)") (class "Default")
      (node (ref "ML") (pin "126") (pinfunction "PG11_126") (pintype "unspecified+no_connect"))
    )
    (net (code "127") (name "unconnected-(ML-PG12-Pad127)") (class "Default")
      (node (ref "ML") (pin "127") (pinfunction "PG12_127") (pintype "unspecified+no_connect"))
    )
    (net (code "128") (name "unconnected-(ML-PG13-Pad128)") (class "Default")
      (node (ref "ML") (pin "128") (pinfunction "PG13_128") (pintype "unspecified+no_connect"))
    )
    (net (code "129") (name "unconnected-(ML-PG14-Pad129)") (class "Default")
      (node (ref "ML") (pin "129") (pinfunction "PG14_129") (pintype "unspecified+no_connect"))
    )
    (net (code "130") (name "unconnected-(ML-PG15-Pad132)") (class "Default")
      (node (ref "ML") (pin "132") (pinfunction "PG15_132") (pintype "unspecified+no_connect"))
    )
    (net (code "131") (name "unconnected-(ML-VREF+-Pad32)") (class "Default")
      (node (ref "ML") (pin "32") (pinfunction "VREF+_32") (pintype "unspecified+no_connect"))
    )
  )
)
